# AU.net
KiCad netlist of a schematic drawn in Altium Designer
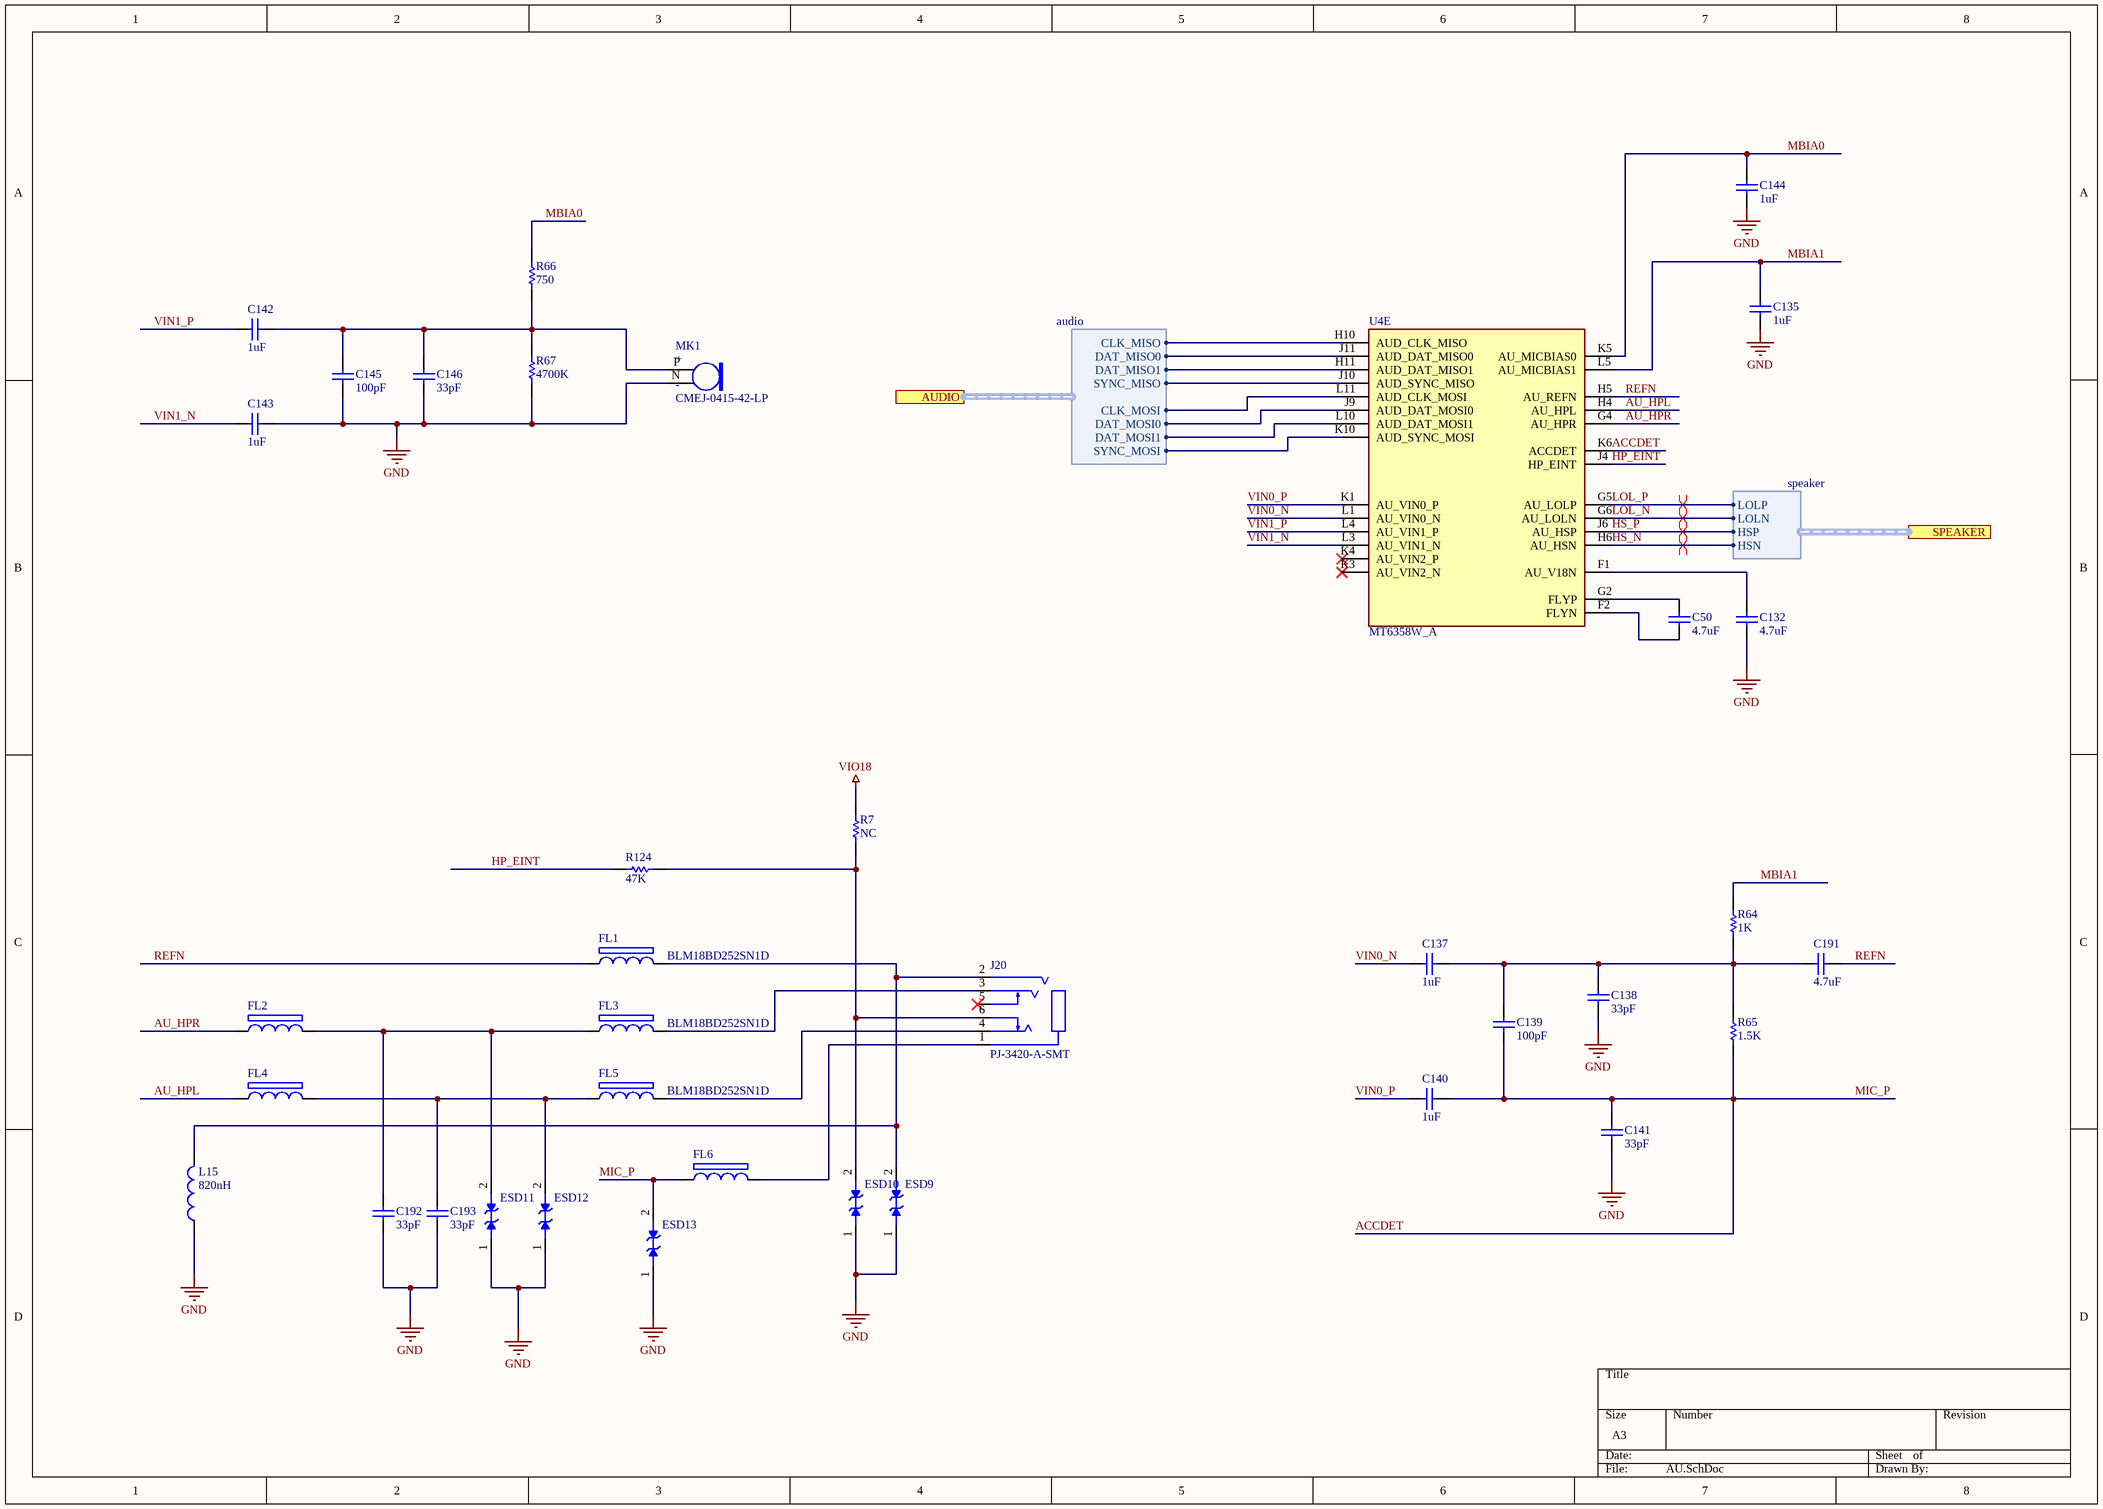
[diagram p0: AU.SchDoc]

(export (version "E")
  (design (tool "Eeschema 10.0.6"))
  (components
    (comp (ref "C50")
      (value "4.7uF")
      (footprint "C0805")
      (fields (field (name "Comment") "C0805"))
      (libsource (lib "kit") (part "C0805"))
    )
    (comp (ref "C132")
      (value "4.7uF")
      (footprint "C0805")
      (fields (field (name "Comment") "C0805"))
      (libsource (lib "kit") (part "C0805"))
    )
    (comp (ref "C135")
      (value "1uF")
      (footprint "C0805")
      (fields (field (name "Comment") "C0805"))
      (libsource (lib "kit") (part "C0805"))
    )
    (comp (ref "C137")
      (value "1uF")
      (footprint "C0805")
      (fields (field (name "Comment") "C0805"))
      (libsource (lib "kit") (part "C0805"))
    )
    (comp (ref "C138")
      (value "33pF")
      (footprint "C0402")
      (fields (field (name "Comment") "C0402"))
      (libsource (lib "kit") (part "C0402"))
    )
    (comp (ref "C139")
      (value "100pF")
      (footprint "C0402")
      (fields (field (name "Comment") "C0402"))
      (libsource (lib "kit") (part "C0402"))
    )
    (comp (ref "C140")
      (value "1uF")
      (footprint "C0805")
      (fields (field (name "Comment") "C0805"))
      (libsource (lib "kit") (part "C0805"))
    )
    (comp (ref "C141")
      (value "33pF")
      (footprint "C0402")
      (fields (field (name "Comment") "C0402"))
      (libsource (lib "kit") (part "C0402"))
    )
    (comp (ref "C142")
      (value "1uF")
      (footprint "C0805")
      (fields (field (name "Comment") "C0805"))
      (libsource (lib "kit") (part "C0805"))
    )
    (comp (ref "C143")
      (value "1uF")
      (footprint "C0805")
      (fields (field (name "Comment") "C0805"))
      (libsource (lib "kit") (part "C0805"))
    )
    (comp (ref "C144")
      (value "1uF")
      (footprint "C0805")
      (fields (field (name "Comment") "C0805"))
      (libsource (lib "kit") (part "C0805"))
    )
    (comp (ref "C145")
      (value "100pF")
      (footprint "C0402")
      (fields (field (name "Comment") "C0402"))
      (libsource (lib "kit") (part "C0402"))
    )
    (comp (ref "C146")
      (value "33pF")
      (footprint "C0402")
      (fields (field (name "Comment") "C0402"))
      (libsource (lib "kit") (part "C0402"))
    )
    (comp (ref "C191")
      (value "4.7uF")
      (footprint "C0805")
      (fields (field (name "Comment") "C0805"))
      (libsource (lib "kit") (part "C0805"))
    )
    (comp (ref "C192")
      (value "33pF")
      (footprint "C0402")
      (fields (field (name "Comment") "C0402"))
      (libsource (lib "kit") (part "C0402"))
    )
    (comp (ref "C193")
      (value "33pF")
      (footprint "C0402")
      (fields (field (name "Comment") "C0402"))
      (libsource (lib "kit") (part "C0402"))
    )
    (comp (ref "ESD9")
      (value "ESD9B5.0ST5G")
      (footprint "SODFL1006X40N")
      (description "Clamp Ipp Tvs Diode Surface Mount SOD-923")
      (libsource (lib "kit") (part "ESD9B5.0ST5G"))
    )
    (comp (ref "ESD10")
      (value "ESD9B5.0ST5G")
      (footprint "SODFL1006X40N")
      (description "Clamp Ipp Tvs Diode Surface Mount SOD-923")
      (libsource (lib "kit") (part "ESD9B5.0ST5G"))
    )
    (comp (ref "ESD11")
      (value "ESD9B5.0ST5G")
      (footprint "SODFL1006X40N")
      (description "Clamp Ipp Tvs Diode Surface Mount SOD-923")
      (libsource (lib "kit") (part "ESD9B5.0ST5G"))
    )
    (comp (ref "ESD12")
      (value "ESD9B5.0ST5G")
      (footprint "SODFL1006X40N")
      (description "Clamp Ipp Tvs Diode Surface Mount SOD-923")
      (libsource (lib "kit") (part "ESD9B5.0ST5G"))
    )
    (comp (ref "ESD13")
      (value "ESD9B5.0ST5G")
      (footprint "SODFL1006X40N")
      (description "Clamp Ipp Tvs Diode Surface Mount SOD-923")
      (libsource (lib "kit") (part "ESD9B5.0ST5G"))
    )
    (comp (ref "FL1")
      (value "BLM18BD252SN1D")
      (footprint "BEADC1608X95N")
      (description "Inductor Chip Bead 2.5KOhm 25% 100MHz Ferrite 50mA 0603")
      (libsource (lib "kit") (part "BLM18BD252SN1D"))
    )
    (comp (ref "FL2")
      (value "BLM18BD252SN1D")
      (footprint "BEADC1608X95N")
      (description "Inductor Chip Bead 2.5KOhm 25% 100MHz Ferrite 50mA 0603")
      (libsource (lib "kit") (part "BLM18BD252SN1D"))
    )
    (comp (ref "FL3")
      (value "BLM18BD252SN1D")
      (footprint "BEADC1608X95N")
      (description "Inductor Chip Bead 2.5KOhm 25% 100MHz Ferrite 50mA 0603")
      (libsource (lib "kit") (part "BLM18BD252SN1D"))
    )
    (comp (ref "FL4")
      (value "BLM18BD252SN1D")
      (footprint "BEADC1608X95N")
      (description "Inductor Chip Bead 2.5KOhm 25% 100MHz Ferrite 50mA 0603")
      (libsource (lib "kit") (part "BLM18BD252SN1D"))
    )
    (comp (ref "FL5")
      (value "BLM18BD252SN1D")
      (footprint "BEADC1608X95N")
      (description "Inductor Chip Bead 2.5KOhm 25% 100MHz Ferrite 50mA 0603")
      (libsource (lib "kit") (part "BLM18BD252SN1D"))
    )
    (comp (ref "FL6")
      (value "BLM18BD252SN1D")
      (footprint "BEADC1608X95N")
      (description "Inductor Chip Bead 2.5KOhm 25% 100MHz Ferrite 50mA 0603")
      (libsource (lib "kit") (part "BLM18BD252SN1D"))
    )
    (comp (ref "J20")
      (value "PJ-3420-A-SMT")
      (footprint "PJ3420ASMT")
      (description "Connector")
      (libsource (lib "kit") (part "PJ-3420-A-SMT"))
    )
    (comp (ref "L15")
      (value "820nH")
      (footprint "L0603")
      (fields (field (name "Comment") "L0603"))
      (libsource (lib "kit") (part "L0603"))
    )
    (comp (ref "MK1")
      (value "CMEJ-0415-42-LP")
      (footprint "MIC_CMEJ-0415-42-LP")
      (description "4.0 mm, Omnidirectional, PCB Mount, 2.0 Vdc, Elecret Condenser Microphone")
      (libsource (lib "kit") (part "CMEJ-0415-42-LP"))
    )
    (comp (ref "R7")
      (value "NC")
      (footprint "R0603")
      (fields (field (name "Comment") "R0603"))
      (libsource (lib "kit") (part "R0603"))
    )
    (comp (ref "R64")
      (value "1K")
      (footprint "R0603")
      (fields (field (name "Comment") "R0603"))
      (libsource (lib "kit") (part "R0603"))
    )
    (comp (ref "R65")
      (value "1.5K")
      (footprint "R0603")
      (fields (field (name "Comment") "R0603"))
      (libsource (lib "kit") (part "R0603"))
    )
    (comp (ref "R66")
      (value "750")
      (footprint "R0603")
      (fields (field (name "Comment") "R0603"))
      (libsource (lib "kit") (part "R0603"))
    )
    (comp (ref "R67")
      (value "4700K")
      (footprint "R0603")
      (fields (field (name "Comment") "R0603"))
      (libsource (lib "kit") (part "R0603"))
    )
    (comp (ref "R124")
      (value "47K")
      (footprint "R0603")
      (fields (field (name "Comment") "R0603"))
      (libsource (lib "kit") (part "R0603"))
    )
    (comp (ref "U4")
      (value "MT6358W_A")
      (footprint "BGA194C40P16X15_640X600X66")
      (description "PMIC")
      (fields
        (field (name "MANUFACTURER_PART_NUMBER") "MT6358W/A")
        (field (name "MOUSER PART NUMBER") "840-MT6358W/A")
      )
      (libsource (lib "kit") (part "MT6358W_A"))
    )
  )
  (nets
    (net (code "3") (name "/ACCDET") (class "Default")
      (node (ref "C139") (pin "1") (pinfunction "1_1") (pintype "passive"))
      (node (ref "C140") (pin "1") (pinfunction "1_1") (pintype "passive"))
      (node (ref "C141") (pin "2") (pinfunction "2_2") (pintype "passive"))
      (node (ref "ESD13") (pin "2") (pinfunction "A1_2") (pintype "passive"))
      (node (ref "FL6") (pin "1") (pinfunction "1_1") (pintype "passive"))
      (node (ref "R65") (pin "1") (pinfunction "1_1") (pintype "passive"))
      (node (ref "U4") (pin "K6") (pinfunction "ACCDET_K6") (pintype "passive"))
    )
    (net (code "4") (name "/AU_HPL") (class "Default")
      (node (ref "FL4") (pin "1") (pinfunction "1_1") (pintype "passive"))
      (node (ref "U4") (pin "H4") (pinfunction "AU_HPL_H4") (pintype "passive"))
    )
    (net (code "5") (name "/AU_HPR") (class "Default")
      (node (ref "FL2") (pin "1") (pinfunction "1_1") (pintype "passive"))
      (node (ref "U4") (pin "G4") (pinfunction "AU_HPR_G4") (pintype "passive"))
    )
    (net (code "6") (name "/CLK_MISO") (class "Default")
      (node (ref "U4") (pin "H10") (pinfunction "AUD_CLK_MISO_H10") (pintype "passive"))
    )
    (net (code "7") (name "/CLK_MOSI") (class "Default")
      (node (ref "U4") (pin "L11") (pinfunction "AUD_CLK_MOSI_L11") (pintype "passive"))
    )
    (net (code "8") (name "/DAT_MISO0") (class "Default")
      (node (ref "U4") (pin "J11") (pinfunction "AUD_DAT_MISO0_J11") (pintype "passive"))
    )
    (net (code "9") (name "/DAT_MISO1") (class "Default")
      (node (ref "U4") (pin "H11") (pinfunction "AUD_DAT_MISO1_H11") (pintype "passive"))
    )
    (net (code "10") (name "/DAT_MOSI0") (class "Default")
      (node (ref "U4") (pin "J9") (pinfunction "AUD_DAT_MOSI0_J9") (pintype "passive"))
    )
    (net (code "11") (name "/DAT_MOSI1") (class "Default")
      (node (ref "U4") (pin "L10") (pinfunction "AUD_DAT_MOSI1_L10") (pintype "passive"))
    )
    (net (code "12") (name "/HP_EINT") (class "Default")
      (node (ref "R124") (pin "1") (pinfunction "1_1") (pintype "passive"))
      (node (ref "U4") (pin "J4") (pinfunction "HP_EINT_J4") (pintype "passive"))
    )
    (net (code "13") (name "/HS_N") (class "Default")
      (node (ref "U4") (pin "H6") (pinfunction "AU_HSN_H6") (pintype "passive"))
    )
    (net (code "14") (name "/HS_P") (class "Default")
      (node (ref "U4") (pin "J6") (pinfunction "AU_HSP_J6") (pintype "passive"))
    )
    (net (code "15") (name "/LOL_N") (class "Default")
      (node (ref "U4") (pin "G6") (pinfunction "AU_LOLN_G6") (pintype "passive"))
    )
    (net (code "16") (name "/LOL_P") (class "Default")
      (node (ref "U4") (pin "G5") (pinfunction "AU_LOLP_G5") (pintype "passive"))
    )
    (net (code "17") (name "/MBIA0") (class "Default")
      (node (ref "C144") (pin "1") (pinfunction "1_1") (pintype "passive"))
      (node (ref "R66") (pin "2") (pinfunction "2_2") (pintype "passive"))
      (node (ref "U4") (pin "K5") (pinfunction "AU_MICBIAS0_K5") (pintype "passive"))
    )
    (net (code "18") (name "/MBIA1") (class "Default")
      (node (ref "C135") (pin "1") (pinfunction "1_1") (pintype "passive"))
      (node (ref "R64") (pin "2") (pinfunction "2_2") (pintype "passive"))
      (node (ref "U4") (pin "L5") (pinfunction "AU_MICBIAS1_L5") (pintype "passive"))
    )
    (net (code "19") (name "/REFN") (class "Default")
      (node (ref "C191") (pin "1") (pinfunction "1_1") (pintype "passive"))
      (node (ref "FL1") (pin "1") (pinfunction "1_1") (pintype "passive"))
      (node (ref "U4") (pin "H5") (pinfunction "AU_REFN_H5") (pintype "passive"))
    )
    (net (code "20") (name "/SYNC_MISO") (class "Default")
      (node (ref "U4") (pin "J10") (pinfunction "AUD_SYNC_MISO_J10") (pintype "passive"))
    )
    (net (code "21") (name "/SYNC_MOSI") (class "Default")
      (node (ref "U4") (pin "K10") (pinfunction "AUD_SYNC_MOSI_K10") (pintype "passive"))
    )
    (net (code "22") (name "/VIN0_N") (class "Default")
      (node (ref "C137") (pin "2") (pinfunction "2_2") (pintype "passive"))
      (node (ref "U4") (pin "L1") (pinfunction "AU_VIN0_N_L1") (pintype "passive"))
    )
    (net (code "23") (name "/VIN0_P") (class "Default")
      (node (ref "C140") (pin "2") (pinfunction "2_2") (pintype "passive"))
      (node (ref "U4") (pin "K1") (pinfunction "AU_VIN0_P_K1") (pintype "passive"))
    )
    (net (code "24") (name "/VIN1_N") (class "Default")
      (node (ref "C143") (pin "2") (pinfunction "2_2") (pintype "passive"))
      (node (ref "U4") (pin "L3") (pinfunction "AU_VIN1_N_L3") (pintype "passive"))
    )
    (net (code "25") (name "/VIN1_P") (class "Default")
      (node (ref "C142") (pin "2") (pinfunction "2_2") (pintype "passive"))
      (node (ref "U4") (pin "L4") (pinfunction "AU_VIN1_P_L4") (pintype "passive"))
    )
    (net (code "28") (name "GND") (class "Default")
      (node (ref "C132") (pin "2") (pinfunction "2_2") (pintype "passive"))
      (node (ref "C135") (pin "2") (pinfunction "2_2") (pintype "passive"))
      (node (ref "C138") (pin "1") (pinfunction "1_1") (pintype "passive"))
      (node (ref "C141") (pin "1") (pinfunction "1_1") (pintype "passive"))
      (node (ref "C143") (pin "1") (pinfunction "1_1") (pintype "passive"))
      (node (ref "C144") (pin "2") (pinfunction "2_2") (pintype "passive"))
      (node (ref "C145") (pin "1") (pinfunction "1_1") (pintype "passive"))
      (node (ref "C146") (pin "1") (pinfunction "1_1") (pintype "passive"))
      (node (ref "C192") (pin "1") (pinfunction "1_1") (pintype "passive"))
      (node (ref "C193") (pin "1") (pinfunction "1_1") (pintype "passive"))
      (node (ref "ESD10") (pin "1") (pinfunction "A_1") (pintype "passive"))
      (node (ref "ESD11") (pin "1") (pinfunction "A_1") (pintype "passive"))
      (node (ref "ESD12") (pin "1") (pinfunction "A_1") (pintype "passive"))
      (node (ref "ESD13") (pin "1") (pinfunction "A_1") (pintype "passive"))
      (node (ref "ESD9") (pin "1") (pinfunction "A_1") (pintype "passive"))
      (node (ref "L15") (pin "1") (pinfunction "1_1") (pintype "passive"))
      (node (ref "MK1") (pin "N") (pinfunction "GND_N") (pintype "passive"))
      (node (ref "R67") (pin "1") (pinfunction "1_1") (pintype "passive"))
    )
    (net (code "29") (name "Net-(C137-Pad1)") (class "Default")
      (node (ref "C137") (pin "1") (pinfunction "1_1") (pintype "passive"))
      (node (ref "C138") (pin "2") (pinfunction "2_2") (pintype "passive"))
      (node (ref "C139") (pin "2") (pinfunction "2_2") (pintype "passive"))
      (node (ref "C191") (pin "2") (pinfunction "2_2") (pintype "passive"))
      (node (ref "R64") (pin "1") (pinfunction "1_1") (pintype "passive"))
      (node (ref "R65") (pin "2") (pinfunction "2_2") (pintype "passive"))
    )
    (net (code "30") (name "Net-(ESD9-A1)") (class "Default")
      (node (ref "ESD9") (pin "2") (pinfunction "A1_2") (pintype "passive"))
      (node (ref "FL1") (pin "2") (pinfunction "2_2") (pintype "passive"))
      (node (ref "J20") (pin "2") (pinfunction "5_2") (pintype "passive"))
      (node (ref "L15") (pin "2") (pinfunction "2_2") (pintype "passive"))
    )
    (net (code "31") (name "Net-(ESD10-A1)") (class "Default")
      (node (ref "ESD10") (pin "2") (pinfunction "A1_2") (pintype "passive"))
      (node (ref "J20") (pin "6") (pinfunction "4_6") (pintype "passive"))
      (node (ref "R124") (pin "2") (pinfunction "2_2") (pintype "passive"))
      (node (ref "R7") (pin "1") (pinfunction "1_1") (pintype "passive"))
    )
    (net (code "32") (name "Net-(ESD11-A1)") (class "Default")
      (node (ref "C192") (pin "2") (pinfunction "2_2") (pintype "passive"))
      (node (ref "ESD11") (pin "2") (pinfunction "A1_2") (pintype "passive"))
      (node (ref "FL2") (pin "2") (pinfunction "2_2") (pintype "passive"))
      (node (ref "FL3") (pin "1") (pinfunction "1_1") (pintype "passive"))
    )
    (net (code "33") (name "Net-(ESD12-A1)") (class "Default")
      (node (ref "C193") (pin "2") (pinfunction "2_2") (pintype "passive"))
      (node (ref "ESD12") (pin "2") (pinfunction "A1_2") (pintype "passive"))
      (node (ref "FL4") (pin "2") (pinfunction "2_2") (pintype "passive"))
      (node (ref "FL5") (pin "1") (pinfunction "1_1") (pintype "passive"))
    )
    (net (code "34") (name "Net-(FL6-Pad2)") (class "Default")
      (node (ref "FL6") (pin "2") (pinfunction "2_2") (pintype "passive"))
      (node (ref "J20") (pin "1") (pinfunction "1_1") (pintype "passive"))
    )
    (net (code "35") (name "Net-(J20-2)") (class "Default")
      (node (ref "FL3") (pin "2") (pinfunction "2_2") (pintype "passive"))
      (node (ref "J20") (pin "3") (pinfunction "2_3") (pintype "passive"))
    )
    (net (code "36") (name "Net-(J20-3)") (class "Default")
      (node (ref "FL5") (pin "2") (pinfunction "2_2") (pintype "passive"))
      (node (ref "J20") (pin "4") (pinfunction "3_4") (pintype "passive"))
    )
    (net (code "37") (name "Net-(MK1-OUTPUT)") (class "Default")
      (node (ref "C142") (pin "1") (pinfunction "1_1") (pintype "passive"))
      (node (ref "C145") (pin "2") (pinfunction "2_2") (pintype "passive"))
      (node (ref "C146") (pin "2") (pinfunction "2_2") (pintype "passive"))
      (node (ref "MK1") (pin "P") (pinfunction "OUTPUT_P") (pintype "passive"))
      (node (ref "R66") (pin "1") (pinfunction "1_1") (pintype "passive"))
      (node (ref "R67") (pin "2") (pinfunction "2_2") (pintype "passive"))
    )
    (net (code "38") (name "Net-(U4E-AU_V18N)") (class "Default")
      (node (ref "C132") (pin "1") (pinfunction "1_1") (pintype "passive"))
      (node (ref "U4") (pin "F1") (pinfunction "AU_V18N_F1") (pintype "passive"))
    )
    (net (code "39") (name "Net-(U4E-FLYN)") (class "Default")
      (node (ref "C50") (pin "2") (pinfunction "2_2") (pintype "passive"))
      (node (ref "U4") (pin "F2") (pinfunction "FLYN_F2") (pintype "passive"))
    )
    (net (code "40") (name "Net-(U4E-FLYP)") (class "Default")
      (node (ref "C50") (pin "1") (pinfunction "1_1") (pintype "passive"))
      (node (ref "U4") (pin "G2") (pinfunction "FLYP_G2") (pintype "passive"))
    )
    (net (code "41") (name "VIO18") (class "Default")
      (node (ref "R7") (pin "2") (pinfunction "2_2") (pintype "passive"))
    )
    (net (code "42") (name "unconnected-(J20-4-Pad5)") (class "Default")
      (node (ref "J20") (pin "5") (pinfunction "4_5") (pintype "passive+no_connect"))
    )
    (net (code "43") (name "unconnected-(U4E-AU_VIN2_N-PadK3)") (class "Default")
      (node (ref "U4") (pin "K3") (pinfunction "AU_VIN2_N_K3") (pintype "passive+no_connect"))
    )
    (net (code "44") (name "unconnected-(U4E-AU_VIN2_P-PadK4)") (class "Default")
      (node (ref "U4") (pin "K4") (pinfunction "AU_VIN2_P_K4") (pintype "passive+no_connect"))
    )
  )
)
